# 2_Battery.net
KiCad netlist of a schematic drawn in Altium Designer
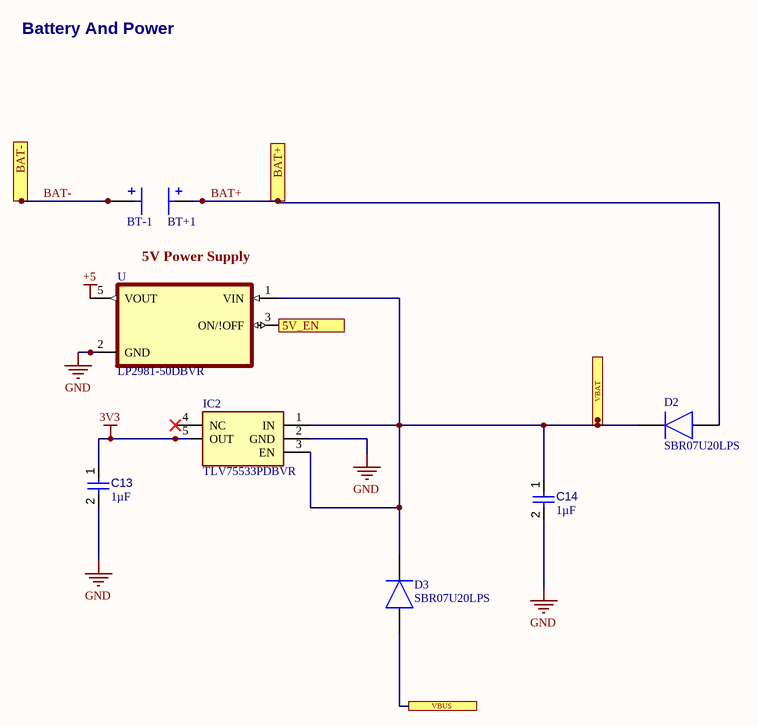
[diagram p0: [2]Battery.SchDoc]

(export (version "E")
  (design (tool "Eeschema 10.0.6"))
  (components
    (comp (ref "BT+1")
      (value "BATTERY CONTACT CLIP A/AA PC PIN")
      (footprint "BAT_BK-82")
      (description "Battery Contact Clip A, AA 1 Cell PC Pin")
      (libsource (lib "PCB_Project") (part "BK-82"))
    )
    (comp (ref "BT-1")
      (value "BATTERY CONTACT CLIP A/AA PC PIN")
      (footprint "BAT_BK-82")
      (description "Battery Contact Clip A, AA 1 Cell PC Pin")
      (libsource (lib "PCB_Project") (part "BK-82"))
    )
    (comp (ref "C13")
      (value "1µF")
      (footprint "CAPC1608X90X40ML10T20")
      (description "Chip Capacitor, 1 uF, +/- 10%, 25 V, 0603 (1608 Metric)")
      (fields (field (name "TOLERANCE") "10%") (field (name "Comment") "Capacitor 1 uF +/- 10% 25 V 0603"))
      (libsource (lib "Latium Technologies") (part "CAP-NP-2"))
    )
    (comp (ref "C14")
      (value "1µF")
      (footprint "CAPC1608X90X40ML10T20")
      (description "Chip Capacitor, 1 uF, +/- 10%, 25 V, 0603 (1608 Metric)")
      (fields (field (name "TOLERANCE") "10%") (field (name "Comment") "Capacitor 1 uF +/- 10% 25 V 0603"))
      (libsource (lib "Latium Technologies") (part "CAP-NP-2"))
    )
    (comp (ref "D2")
      (value "SBR07U20LPS")
      (footprint "CDBQR70HF")
      (description "Diode")
      (fields
        (field (name "MANUFACTURER_PART_NUMBER") "CDSQR4148-HF")
        (field (name "MOUSER PART NUMBER") "750-CDSQR4148-HF")
      )
      (libsource (lib "Schlib_For_High_Voltage_Sensor") (part "CDSQR4148-HF_1"))
    )
    (comp (ref "D3")
      (value "SBR07U20LPS")
      (footprint "CDBQR70HF")
      (description "Diode")
      (fields
        (field (name "MANUFACTURER_PART_NUMBER") "CDSQR4148-HF")
        (field (name "MOUSER PART NUMBER") "750-CDSQR4148-HF")
      )
      (libsource (lib "Schlib_For_High_Voltage_Sensor") (part "CDSQR4148-HF_1"))
    )
    (comp (ref "IC2")
      (value "TLV75533PDBVR")
      (footprint "SOT95P280X145-5N")
      (description "Integrated Circuit")
      (fields (field (name "MOUSER PART NUMBER") "595-TLV75533PDBVR"))
      (libsource (lib "PCB_Project") (part "TLV75533PDBVR"))
    )
    (comp (ref "U")
      (value "LP2981-50DBVR")
      (footprint "PcbLibForHigh_Voltage_Sensor:SOT95P280X145-5N")
      (description "100-mA, 16-V, low-dropout voltage regulator with enable 5-SOT-23 -40 to 125")
      (fields (field (name "MF") "Texas Instruments"))
      (libsource (lib "Schlib_For_High_Voltage_Sensor") (part "LP2981-50DBVR"))
    )
  )
  (nets
    (net (code "1") (name "+5") (class "Default")
      (node (ref "U") (pin "5") (pinfunction "VOUT_5") (pintype "output"))
    )
    (net (code "2") (name "/5V_EN") (class "Default")
      (node (ref "U") (pin "3") (pinfunction "ON/!OFF_3") (pintype "bidirectional"))
    )
    (net (code "3") (name "/BAT+") (class "Default")
      (node (ref "BT+1") (pin "S1") (pinfunction "POS_S1") (pintype "passive"))
      (node (ref "BT+1") (pin "S2") (pinfunction "POS_S2") (pintype "passive"))
      (node (ref "D2") (pin "2") (pinfunction "A_2") (pintype "passive"))
    )
    (net (code "4") (name "/BAT-") (class "Default")
      (node (ref "BT-1") (pin "S1") (pinfunction "POS_S1") (pintype "passive"))
      (node (ref "BT-1") (pin "S2") (pinfunction "POS_S2") (pintype "passive"))
    )
    (net (code "5") (name "/VBAT") (class "Default")
      (node (ref "C14") (pin "1") (pinfunction "1_1") (pintype "passive"))
      (node (ref "D2") (pin "1") (pinfunction "K_1") (pintype "passive"))
      (node (ref "D3") (pin "1") (pinfunction "K_1") (pintype "passive"))
      (node (ref "IC2") (pin "1") (pinfunction "IN_1") (pintype "passive"))
      (node (ref "IC2") (pin "3") (pinfunction "EN_3") (pintype "passive"))
      (node (ref "U") (pin "1") (pinfunction "VIN_1") (pintype "input"))
    )
    (net (code "6") (name "/VBUS") (class "Default")
      (node (ref "D3") (pin "2") (pinfunction "A_2") (pintype "passive"))
    )
    (net (code "7") (name "3V3") (class "Default")
      (node (ref "C13") (pin "1") (pinfunction "1_1") (pintype "passive"))
      (node (ref "IC2") (pin "5") (pinfunction "OUT_5") (pintype "passive"))
    )
    (net (code "8") (name "GND") (class "Default")
      (node (ref "C13") (pin "2") (pinfunction "2_2") (pintype "passive"))
      (node (ref "C14") (pin "2") (pinfunction "2_2") (pintype "passive"))
      (node (ref "IC2") (pin "2") (pinfunction "GND_2") (pintype "passive"))
      (node (ref "U") (pin "2") (pinfunction "GND_2") (pintype "power_in"))
    )
    (net (code "9") (name "unconnected-(IC2-NC-Pad4)") (class "Default")
      (node (ref "IC2") (pin "4") (pinfunction "NC_4") (pintype "passive+no_connect"))
    )
  )
)
